# Led_lane_EasyEDA_PRO.net
KiCad netlist of a schematic drawn in EasyEDA Pro
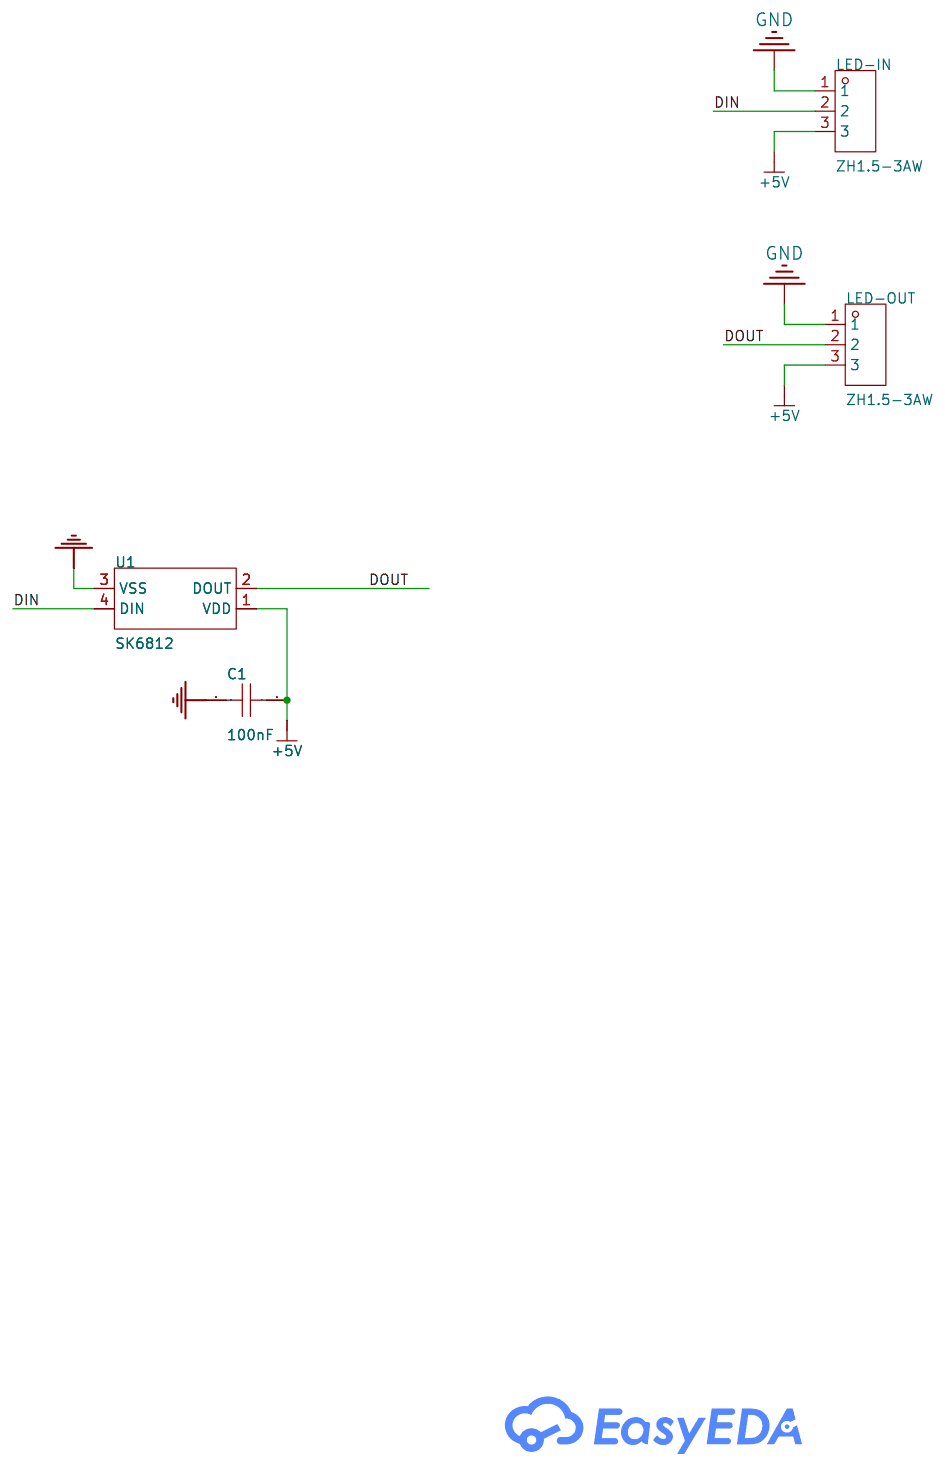
[diagram p0: schematic sheet]

(export (version "E")
  (design (tool "Eeschema 10.0.6"))
  (components
    (comp (ref "C1")
      (value "100nF")
      (footprint "easyedapro:C0603")
      (libsource (lib "easyedapro") (part "CAP"))
    )
    (comp (ref "LED-IN")
      (value "ZH1.5-3AW")
      (footprint "easyedapro:CONN-TH_ZH1.5-3AW")
      (fields (field (name "Manufacturer") "CAX(创都)"))
      (libsource (lib "easyedapro") (part "ZH1.5-3AW_C722915"))
    )
    (comp (ref "LED-OUT")
      (value "ZH1.5-3AW")
      (footprint "easyedapro:CONN-TH_ZH1.5-3AW")
      (fields (field (name "Manufacturer") "CAX(创都)"))
      (libsource (lib "easyedapro") (part "ZH1.5-3AW_C722915"))
    )
    (comp (ref "U1")
      (value "SK6812")
      (footprint "easyedapro:LED-SMD_4P-L5.0-W5.0-LS5.4-TL-1")
      (fields (field (name "Manufacturer") "欧思科光电"))
      (libsource (lib "easyedapro") (part "SK6812_C5378720"))
    )
  )
  (nets
    (net (code "1") (name "+5V") (class "Default")
      (node (ref "C1") (pin "1") (pinfunction "1_1") (pintype "input"))
      (node (ref "LED-IN") (pin "3") (pinfunction "3_3") (pintype "unspecified"))
      (node (ref "LED-OUT") (pin "3") (pinfunction "3_3") (pintype "unspecified"))
      (node (ref "U1") (pin "1") (pinfunction "VDD_1") (pintype "unspecified"))
    )
    (net (code "2") (name "/DIN") (class "Default")
      (node (ref "LED-IN") (pin "2") (pinfunction "2_2") (pintype "unspecified"))
      (node (ref "U1") (pin "4") (pinfunction "DIN_4") (pintype "unspecified"))
    )
    (net (code "3") (name "/DOUT") (class "Default")
      (node (ref "LED-OUT") (pin "2") (pinfunction "2_2") (pintype "unspecified"))
      (node (ref "U1") (pin "2") (pinfunction "DOUT_2") (pintype "unspecified"))
    )
    (net (code "4") (name "GND") (class "Default")
      (node (ref "C1") (pin "2") (pinfunction "2_2") (pintype "input"))
      (node (ref "LED-IN") (pin "1") (pinfunction "1_1") (pintype "unspecified"))
      (node (ref "LED-OUT") (pin "1") (pinfunction "1_1") (pintype "unspecified"))
      (node (ref "U1") (pin "3") (pinfunction "VSS_3") (pintype "unspecified"))
    )
  )
)
